# mcu.net
KiCad netlist of a schematic drawn in Altium Designer
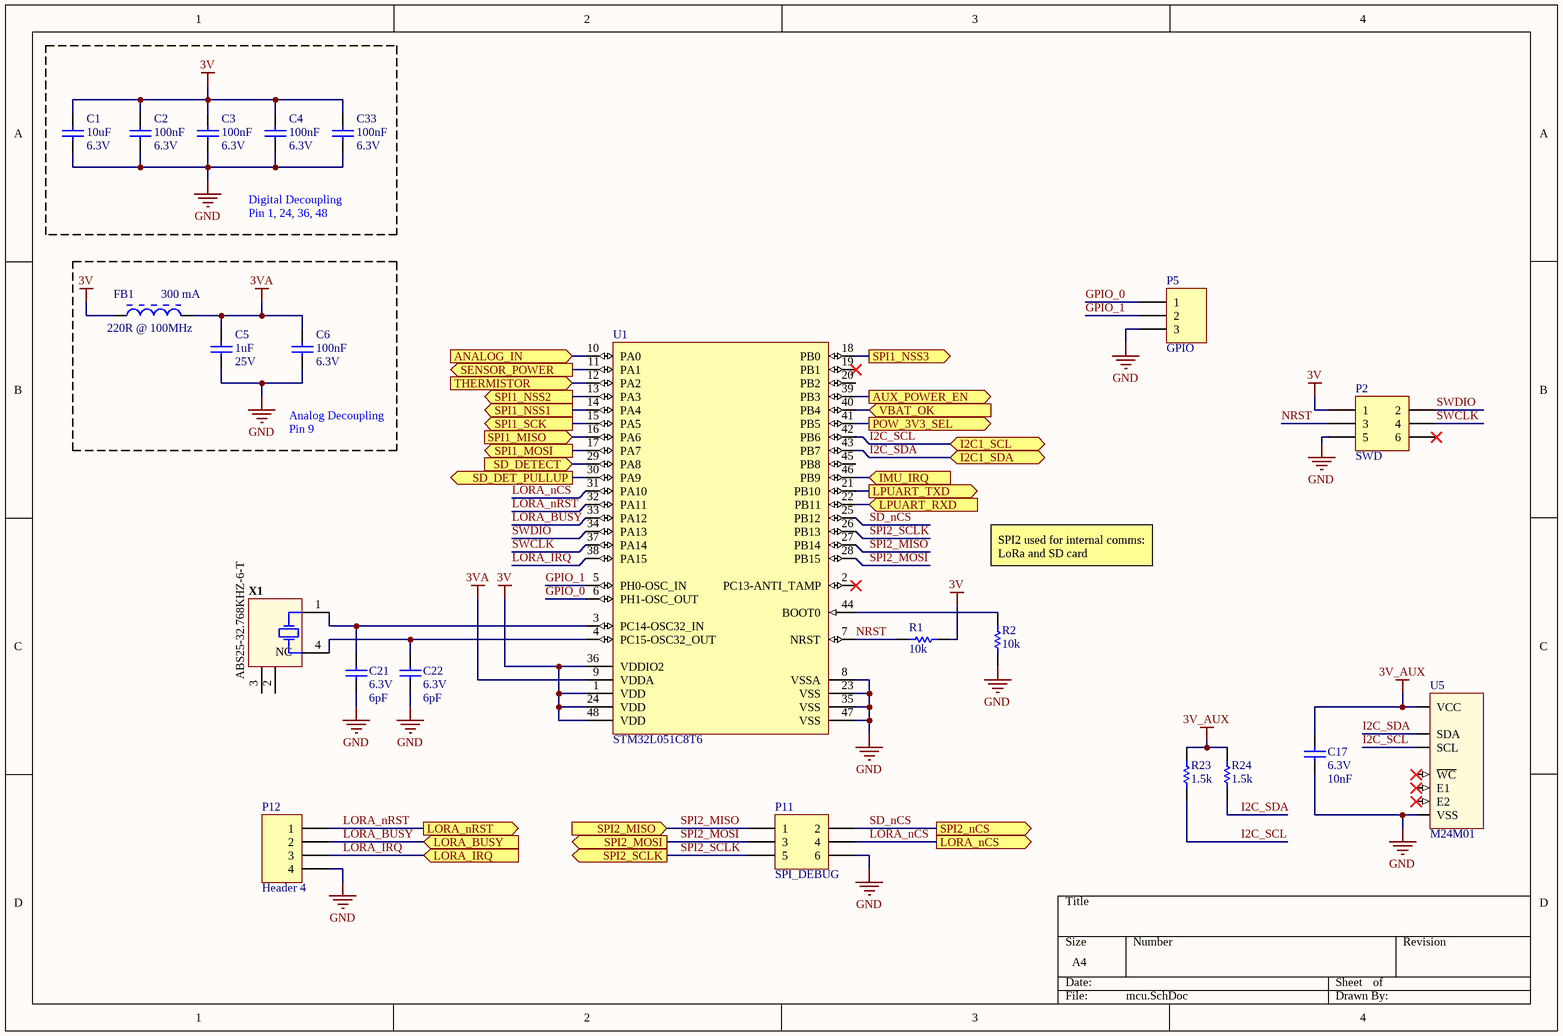
[diagram p0: mcu.SchDoc]

(export (version "E")
  (design (tool "Eeschema 10.0.6"))
  (components
    (comp (ref "C1")
      (value "10uF")
      (footprint "0603 (1608M)")
      (description "Capacitor")
      (fields (field (name "VOLTAGE") "6.3V") (field (name "Comment") "Cap"))
      (libsource (lib "components") (part "Cap"))
    )
    (comp (ref "C2")
      (value "100nF")
      (footprint "0603 (1608M)")
      (description "Capacitor")
      (fields (field (name "VOLTAGE") "6.3V") (field (name "Comment") "Cap"))
      (libsource (lib "components") (part "Cap"))
    )
    (comp (ref "C3")
      (value "100nF")
      (footprint "0603 (1608M)")
      (description "Capacitor")
      (fields (field (name "VOLTAGE") "6.3V") (field (name "Comment") "Cap"))
      (libsource (lib "components") (part "Cap"))
    )
    (comp (ref "C4")
      (value "100nF")
      (footprint "0603 (1608M)")
      (description "Capacitor")
      (fields (field (name "VOLTAGE") "6.3V") (field (name "Comment") "Cap"))
      (libsource (lib "components") (part "Cap"))
    )
    (comp (ref "C5")
      (value "1uF")
      (footprint "0603 (1608M)")
      (description "Capacitor")
      (fields (field (name "VOLTAGE") "25V") (field (name "Comment") "Cap"))
      (libsource (lib "components") (part "Cap"))
    )
    (comp (ref "C6")
      (value "100nF")
      (footprint "0603 (1608M)")
      (description "Capacitor")
      (fields (field (name "VOLTAGE") "6.3V") (field (name "Comment") "Cap"))
      (libsource (lib "components") (part "Cap"))
    )
    (comp (ref "C17")
      (value "10nF")
      (footprint "0603 (1608M)")
      (description "Capacitor")
      (fields (field (name "VOLTAGE") "6.3V") (field (name "Comment") "Cap"))
      (libsource (lib "components") (part "Cap"))
    )
    (comp (ref "C21")
      (value "6pF")
      (footprint "0603 (1608M)")
      (description "Capacitor")
      (fields (field (name "VOLTAGE") "6.3V") (field (name "Comment") "Cap"))
      (libsource (lib "components") (part "Cap"))
    )
    (comp (ref "C22")
      (value "6pF")
      (footprint "0603 (1608M)")
      (description "Capacitor")
      (fields (field (name "VOLTAGE") "6.3V") (field (name "Comment") "Cap"))
      (libsource (lib "components") (part "Cap"))
    )
    (comp (ref "C33")
      (value "100nF")
      (footprint "0603 (1608M)")
      (description "Capacitor")
      (fields (field (name "VOLTAGE") "6.3V") (field (name "Comment") "Cap"))
      (libsource (lib "components") (part "Cap"))
    )
    (comp (ref "FB1")
      (value "BLM15GG221SN1D")
      (footprint "MURA-BLM15-CHIP-2_V")
      (fields
        (field (name "MANUFACTURER") "Murata")
        (field (name "RATED CURRENT") "300 mA")
        (field (name "PARAMETER 1") "220R @ 100MHz")
      )
      (libsource (lib "Altium Content Vault") (part "MURA-FB-2"))
    )
    (comp (ref "P2")
      (value "SWD")
      (footprint "HDR2X3")
      (description "Header, 3-Pin, Dual row")
      (fields (field (name "PUBLISHER") "Altium Limited"))
      (libsource (lib "Miscellaneous Connectors") (part "Header 3X2"))
    )
    (comp (ref "P5")
      (value "GPIO")
      (footprint "HDR1X3")
      (description "Header, 3-Pin")
      (fields (field (name "PUBLISHER") "Altium Limited"))
      (libsource (lib "Miscellaneous Connectors") (part "Header 3"))
    )
    (comp (ref "P11")
      (value "SPI_DEBUG")
      (footprint "HDR2X3")
      (description "Header, 3-Pin, Dual row")
      (fields (field (name "PUBLISHER") "Altium Limited"))
      (libsource (lib "Miscellaneous Connectors") (part "Header 3X2"))
    )
    (comp (ref "P12")
      (value "Header 4")
      (footprint "HDR1X4")
      (description "Header, 4-Pin")
      (fields (field (name "PUBLISHER") "Altium Limited"))
      (libsource (lib "Miscellaneous Connectors") (part "Header 4"))
    )
    (comp (ref "R1")
      (value "10k")
      (footprint "0603 (1608M)")
      (description "Resistor")
      (fields (field (name "TOLERANCE") "5%") (field (name "PUBLISHER") "Altium Limited"))
      (libsource (lib "components") (part "Resistor"))
    )
    (comp (ref "R2")
      (value "10k")
      (footprint "0603 (1608M)")
      (description "Resistor")
      (fields (field (name "TOLERANCE") "5%") (field (name "PUBLISHER") "Altium Limited"))
      (libsource (lib "components") (part "Resistor"))
    )
    (comp (ref "R23")
      (value "1.5k")
      (footprint "0603 (1608M)")
      (description "Resistor")
      (fields (field (name "TOLERANCE") "5%") (field (name "PUBLISHER") "Altium Limited"))
      (libsource (lib "components") (part "Resistor"))
    )
    (comp (ref "R24")
      (value "1.5k")
      (footprint "0603 (1608M)")
      (description "Resistor")
      (fields (field (name "TOLERANCE") "5%") (field (name "PUBLISHER") "Altium Limited"))
      (libsource (lib "components") (part "Resistor"))
    )
    (comp (ref "U1")
      (value "STM32L051C8T6")
      (footprint "STM-LQFP48_L")
      (libsource (lib "Altium Content Vault") (part "STM-STM32L051-LQFP-48"))
    )
    (comp (ref "U5")
      (value "M24M01")
      (footprint "TSSOP-8")
      (description "EEPROM Memory IC 1Mb (128K x 8) I²C 1MHz 500ns 8-TSSOP")
      (libsource (lib "components") (part "M24M01"))
    )
    (comp (ref "X1")
      (value "ABS25-32.768KHZ-6-T")
      (footprint "ABRA-ABS25-4_V")
      (fields (field (name "TOLERANCE") "20PPM") (field (name "MANUFACTURER") "Abracon"))
      (libsource (lib "Altium Content Vault") (part "ABRA-XTAL_1-4-4"))
    )
  )
  (nets
    (net (code "1") (name "/ANALOG_IN") (class "Default")
      (node (ref "U1") (pin "10") (pinfunction "PA0_10") (pintype "bidirectional"))
    )
    (net (code "2") (name "/AUX_POWER_EN") (class "Default")
      (node (ref "U1") (pin "39") (pinfunction "PB3_39") (pintype "bidirectional"))
    )
    (net (code "3") (name "/GPIO_0") (class "Default")
      (node (ref "P5") (pin "1") (pinfunction "1_1") (pintype "passive"))
      (node (ref "U1") (pin "6") (pinfunction "PH1-OSC_OUT_6") (pintype "bidirectional"))
    )
    (net (code "4") (name "/GPIO_1") (class "Default")
      (node (ref "P5") (pin "2") (pinfunction "2_2") (pintype "passive"))
      (node (ref "U1") (pin "5") (pinfunction "PH0-OSC_IN_5") (pintype "bidirectional"))
    )
    (net (code "5") (name "/I2C_SCL") (class "Default")
      (node (ref "R23") (pin "1") (pinfunction "1_1") (pintype "passive"))
      (node (ref "U1") (pin "42") (pinfunction "PB6_42") (pintype "bidirectional"))
      (node (ref "U5") (pin "6") (pinfunction "SCL_6") (pintype "bidirectional"))
    )
    (net (code "6") (name "/I2C_SDA") (class "Default")
      (node (ref "R24") (pin "1") (pinfunction "1_1") (pintype "passive"))
      (node (ref "U1") (pin "43") (pinfunction "PB7_43") (pintype "bidirectional"))
      (node (ref "U5") (pin "5") (pinfunction "SDA_5") (pintype "bidirectional"))
    )
    (net (code "7") (name "/IMU_IRQ") (class "Default")
      (node (ref "U1") (pin "46") (pinfunction "PB9_46") (pintype "bidirectional"))
    )
    (net (code "8") (name "/LORA_BUSY") (class "Default")
      (node (ref "P12") (pin "2") (pinfunction "2_2") (pintype "passive"))
      (node (ref "U1") (pin "33") (pinfunction "PA12_33") (pintype "bidirectional"))
    )
    (net (code "9") (name "/LORA_IRQ") (class "Default")
      (node (ref "P12") (pin "3") (pinfunction "3_3") (pintype "passive"))
      (node (ref "U1") (pin "38") (pinfunction "PA15_38") (pintype "bidirectional"))
    )
    (net (code "10") (name "/LORA_nCS") (class "Default")
      (node (ref "P11") (pin "4") (pinfunction "4_4") (pintype "passive"))
      (node (ref "U1") (pin "31") (pinfunction "PA10_31") (pintype "bidirectional"))
    )
    (net (code "11") (name "/LORA_nRST") (class "Default")
      (node (ref "P12") (pin "1") (pinfunction "1_1") (pintype "passive"))
      (node (ref "U1") (pin "32") (pinfunction "PA11_32") (pintype "bidirectional"))
    )
    (net (code "12") (name "/LPUART_RXD") (class "Default")
      (node (ref "U1") (pin "22") (pinfunction "PB11_22") (pintype "bidirectional"))
    )
    (net (code "13") (name "/LPUART_TXD") (class "Default")
      (node (ref "U1") (pin "21") (pinfunction "PB10_21") (pintype "bidirectional"))
    )
    (net (code "14") (name "/NRST") (class "Default")
      (node (ref "P2") (pin "3") (pinfunction "3_3") (pintype "passive"))
      (node (ref "R1") (pin "2") (pinfunction "2_2") (pintype "passive"))
      (node (ref "U1") (pin "7") (pinfunction "NRST_7") (pintype "bidirectional"))
    )
    (net (code "15") (name "/POW_3V3_SEL") (class "Default")
      (node (ref "U1") (pin "41") (pinfunction "PB5_41") (pintype "bidirectional"))
    )
    (net (code "16") (name "/SD_DETECT") (class "Default")
      (node (ref "U1") (pin "29") (pinfunction "PA8_29") (pintype "bidirectional"))
    )
    (net (code "17") (name "/SD_DET_PULLUP") (class "Default")
      (node (ref "U1") (pin "30") (pinfunction "PA9_30") (pintype "bidirectional"))
    )
    (net (code "18") (name "/SD_nCS") (class "Default")
      (node (ref "P11") (pin "2") (pinfunction "2_2") (pintype "passive"))
      (node (ref "U1") (pin "25") (pinfunction "PB12_25") (pintype "bidirectional"))
    )
    (net (code "19") (name "/SENSOR_POWER") (class "Default")
      (node (ref "U1") (pin "11") (pinfunction "PA1_11") (pintype "bidirectional"))
    )
    (net (code "20") (name "/SPI1_MISO") (class "Default")
      (node (ref "U1") (pin "16") (pinfunction "PA6_16") (pintype "bidirectional"))
    )
    (net (code "21") (name "/SPI1_MOSI") (class "Default")
      (node (ref "U1") (pin "17") (pinfunction "PA7_17") (pintype "bidirectional"))
    )
    (net (code "22") (name "/SPI1_NSS1") (class "Default")
      (node (ref "U1") (pin "14") (pinfunction "PA4_14") (pintype "bidirectional"))
    )
    (net (code "23") (name "/SPI1_NSS2") (class "Default")
      (node (ref "U1") (pin "13") (pinfunction "PA3_13") (pintype "bidirectional"))
    )
    (net (code "24") (name "/SPI1_NSS3") (class "Default")
      (node (ref "U1") (pin "18") (pinfunction "PB0_18") (pintype "bidirectional"))
    )
    (net (code "25") (name "/SPI1_SCK") (class "Default")
      (node (ref "U1") (pin "15") (pinfunction "PA5_15") (pintype "bidirectional"))
    )
    (net (code "26") (name "/SPI2_MISO") (class "Default")
      (node (ref "P11") (pin "1") (pinfunction "1_1") (pintype "passive"))
      (node (ref "U1") (pin "27") (pinfunction "PB14_27") (pintype "bidirectional"))
    )
    (net (code "27") (name "/SPI2_MOSI") (class "Default")
      (node (ref "P11") (pin "3") (pinfunction "3_3") (pintype "passive"))
      (node (ref "U1") (pin "28") (pinfunction "PB15_28") (pintype "bidirectional"))
    )
    (net (code "28") (name "/SPI2_SCLK") (class "Default")
      (node (ref "P11") (pin "5") (pinfunction "5_5") (pintype "passive"))
      (node (ref "U1") (pin "26") (pinfunction "PB13_26") (pintype "bidirectional"))
    )
    (net (code "29") (name "/SWCLK") (class "Default")
      (node (ref "P2") (pin "4") (pinfunction "4_4") (pintype "passive"))
      (node (ref "U1") (pin "37") (pinfunction "PA14_37") (pintype "bidirectional"))
    )
    (net (code "30") (name "/SWDIO") (class "Default")
      (node (ref "P2") (pin "2") (pinfunction "2_2") (pintype "passive"))
      (node (ref "U1") (pin "34") (pinfunction "PA13_34") (pintype "bidirectional"))
    )
    (net (code "31") (name "/THERMISTOR") (class "Default")
      (node (ref "U1") (pin "12") (pinfunction "PA2_12") (pintype "bidirectional"))
    )
    (net (code "32") (name "/VBAT_OK") (class "Default")
      (node (ref "U1") (pin "40") (pinfunction "PB4_40") (pintype "bidirectional"))
    )
    (net (code "33") (name "3V") (class "Default")
      (node (ref "C1") (pin "2") (pinfunction "2_2") (pintype "passive"))
      (node (ref "C2") (pin "2") (pinfunction "2_2") (pintype "passive"))
      (node (ref "C3") (pin "2") (pinfunction "2_2") (pintype "passive"))
      (node (ref "C33") (pin "2") (pinfunction "2_2") (pintype "passive"))
      (node (ref "C4") (pin "2") (pinfunction "2_2") (pintype "passive"))
      (node (ref "FB1") (pin "2") (pinfunction "2_2") (pintype "passive"))
      (node (ref "P2") (pin "1") (pinfunction "1_1") (pintype "passive"))
      (node (ref "R1") (pin "1") (pinfunction "1_1") (pintype "passive"))
      (node (ref "U1") (pin "1") (pinfunction "VDD_1") (pintype "power_in"))
      (node (ref "U1") (pin "24") (pinfunction "VDD_24") (pintype "power_in"))
      (node (ref "U1") (pin "36") (pinfunction "VDDIO2_36") (pintype "power_in"))
      (node (ref "U1") (pin "48") (pinfunction "VDD_48") (pintype "power_in"))
    )
    (net (code "34") (name "3VA") (class "Default")
      (node (ref "C5") (pin "2") (pinfunction "2_2") (pintype "passive"))
      (node (ref "C6") (pin "2") (pinfunction "2_2") (pintype "passive"))
      (node (ref "FB1") (pin "1") (pinfunction "1_1") (pintype "passive"))
      (node (ref "U1") (pin "9") (pinfunction "VDDA_9") (pintype "power_in"))
    )
    (net (code "35") (name "3V_AUX") (class "Default")
      (node (ref "C17") (pin "2") (pinfunction "2_2") (pintype "passive"))
      (node (ref "R23") (pin "2") (pinfunction "2_2") (pintype "passive"))
      (node (ref "R24") (pin "2") (pinfunction "2_2") (pintype "passive"))
      (node (ref "U5") (pin "8") (pinfunction "VCC_8") (pintype "power_in"))
    )
    (net (code "36") (name "GND") (class "Default")
      (node (ref "C1") (pin "1") (pinfunction "1_1") (pintype "passive"))
      (node (ref "C17") (pin "1") (pinfunction "1_1") (pintype "passive"))
      (node (ref "C2") (pin "1") (pinfunction "1_1") (pintype "passive"))
      (node (ref "C21") (pin "1") (pinfunction "1_1") (pintype "passive"))
      (node (ref "C22") (pin "1") (pinfunction "1_1") (pintype "passive"))
      (node (ref "C3") (pin "1") (pinfunction "1_1") (pintype "passive"))
      (node (ref "C33") (pin "1") (pinfunction "1_1") (pintype "passive"))
      (node (ref "C4") (pin "1") (pinfunction "1_1") (pintype "passive"))
      (node (ref "C5") (pin "1") (pinfunction "1_1") (pintype "passive"))
      (node (ref "C6") (pin "1") (pinfunction "1_1") (pintype "passive"))
      (node (ref "P11") (pin "6") (pinfunction "6_6") (pintype "passive"))
      (node (ref "P12") (pin "4") (pinfunction "4_4") (pintype "passive"))
      (node (ref "P2") (pin "5") (pinfunction "5_5") (pintype "passive"))
      (node (ref "P5") (pin "3") (pinfunction "3_3") (pintype "passive"))
      (node (ref "R2") (pin "1") (pinfunction "1_1") (pintype "passive"))
      (node (ref "U1") (pin "23") (pinfunction "VSS_23") (pintype "power_in"))
      (node (ref "U1") (pin "35") (pinfunction "VSS_35") (pintype "power_in"))
      (node (ref "U1") (pin "47") (pinfunction "VSS_47") (pintype "power_in"))
      (node (ref "U1") (pin "8") (pinfunction "VSSA_8") (pintype "power_in"))
      (node (ref "U5") (pin "4") (pinfunction "VSS_4") (pintype "power_in"))
    )
    (net (code "37") (name "Net-(U1-BOOT0)") (class "Default")
      (node (ref "R2") (pin "2") (pinfunction "2_2") (pintype "passive"))
      (node (ref "U1") (pin "44") (pinfunction "BOOT0_44") (pintype "input"))
    )
    (net (code "38") (name "Net-(U1-PC14-OSC32_IN)") (class "Default")
      (node (ref "C21") (pin "2") (pinfunction "2_2") (pintype "passive"))
      (node (ref "U1") (pin "3") (pinfunction "PC14-OSC32_IN_3") (pintype "bidirectional"))
      (node (ref "X1") (pin "1") (pinfunction "X1_1") (pintype "passive"))
    )
    (net (code "39") (name "Net-(U1-PC15-OSC32_OUT)") (class "Default")
      (node (ref "C22") (pin "2") (pinfunction "2_2") (pintype "passive"))
      (node (ref "U1") (pin "4") (pinfunction "PC15-OSC32_OUT_4") (pintype "bidirectional"))
      (node (ref "X1") (pin "4") (pinfunction "X2_4") (pintype "passive"))
    )
    (net (code "40") (name "unconnected-(P2-Pad6)") (class "Default")
      (node (ref "P2") (pin "6") (pinfunction "6_6") (pintype "passive+no_connect"))
    )
    (net (code "41") (name "unconnected-(U1-PB1-Pad19)") (class "Default")
      (node (ref "U1") (pin "19") (pinfunction "PB1_19") (pintype "bidirectional+no_connect"))
    )
    (net (code "42") (name "unconnected-(U1-PB2-Pad20)") (class "Default")
      (node (ref "U1") (pin "20") (pinfunction "PB2_20") (pintype "bidirectional"))
    )
    (net (code "43") (name "unconnected-(U1-PB8-Pad45)") (class "Default")
      (node (ref "U1") (pin "45") (pinfunction "PB8_45") (pintype "bidirectional"))
    )
    (net (code "44") (name "unconnected-(U1-PC13-ANTI_TAMP-Pad2)") (class "Default")
      (node (ref "U1") (pin "2") (pinfunction "PC13-ANTI_TAMP_2") (pintype "bidirectional+no_connect"))
    )
    (net (code "45") (name "unconnected-(U5-E1-Pad2)") (class "Default")
      (node (ref "U5") (pin "2") (pinfunction "E1_2") (pintype "input+no_connect"))
    )
    (net (code "46") (name "unconnected-(U5-E2-Pad3)") (class "Default")
      (node (ref "U5") (pin "3") (pinfunction "E2_3") (pintype "input+no_connect"))
    )
    (net (code "47") (name "unconnected-(U5-~{WC}-Pad7)") (class "Default")
      (node (ref "U5") (pin "7") (pinfunction "~{WC}_7") (pintype "input+no_connect"))
    )
    (net (code "48") (name "unconnected-(X1-NC-Pad2)") (class "Default")
      (node (ref "X1") (pin "2") (pinfunction "NC_2") (pintype "passive"))
    )
    (net (code "49") (name "unconnected-(X1-NC-Pad3)") (class "Default")
      (node (ref "X1") (pin "3") (pinfunction "NC_3") (pintype "passive"))
    )
  )
)
